# RS_Analog.net
KiCad netlist of a schematic drawn in Altium Designer
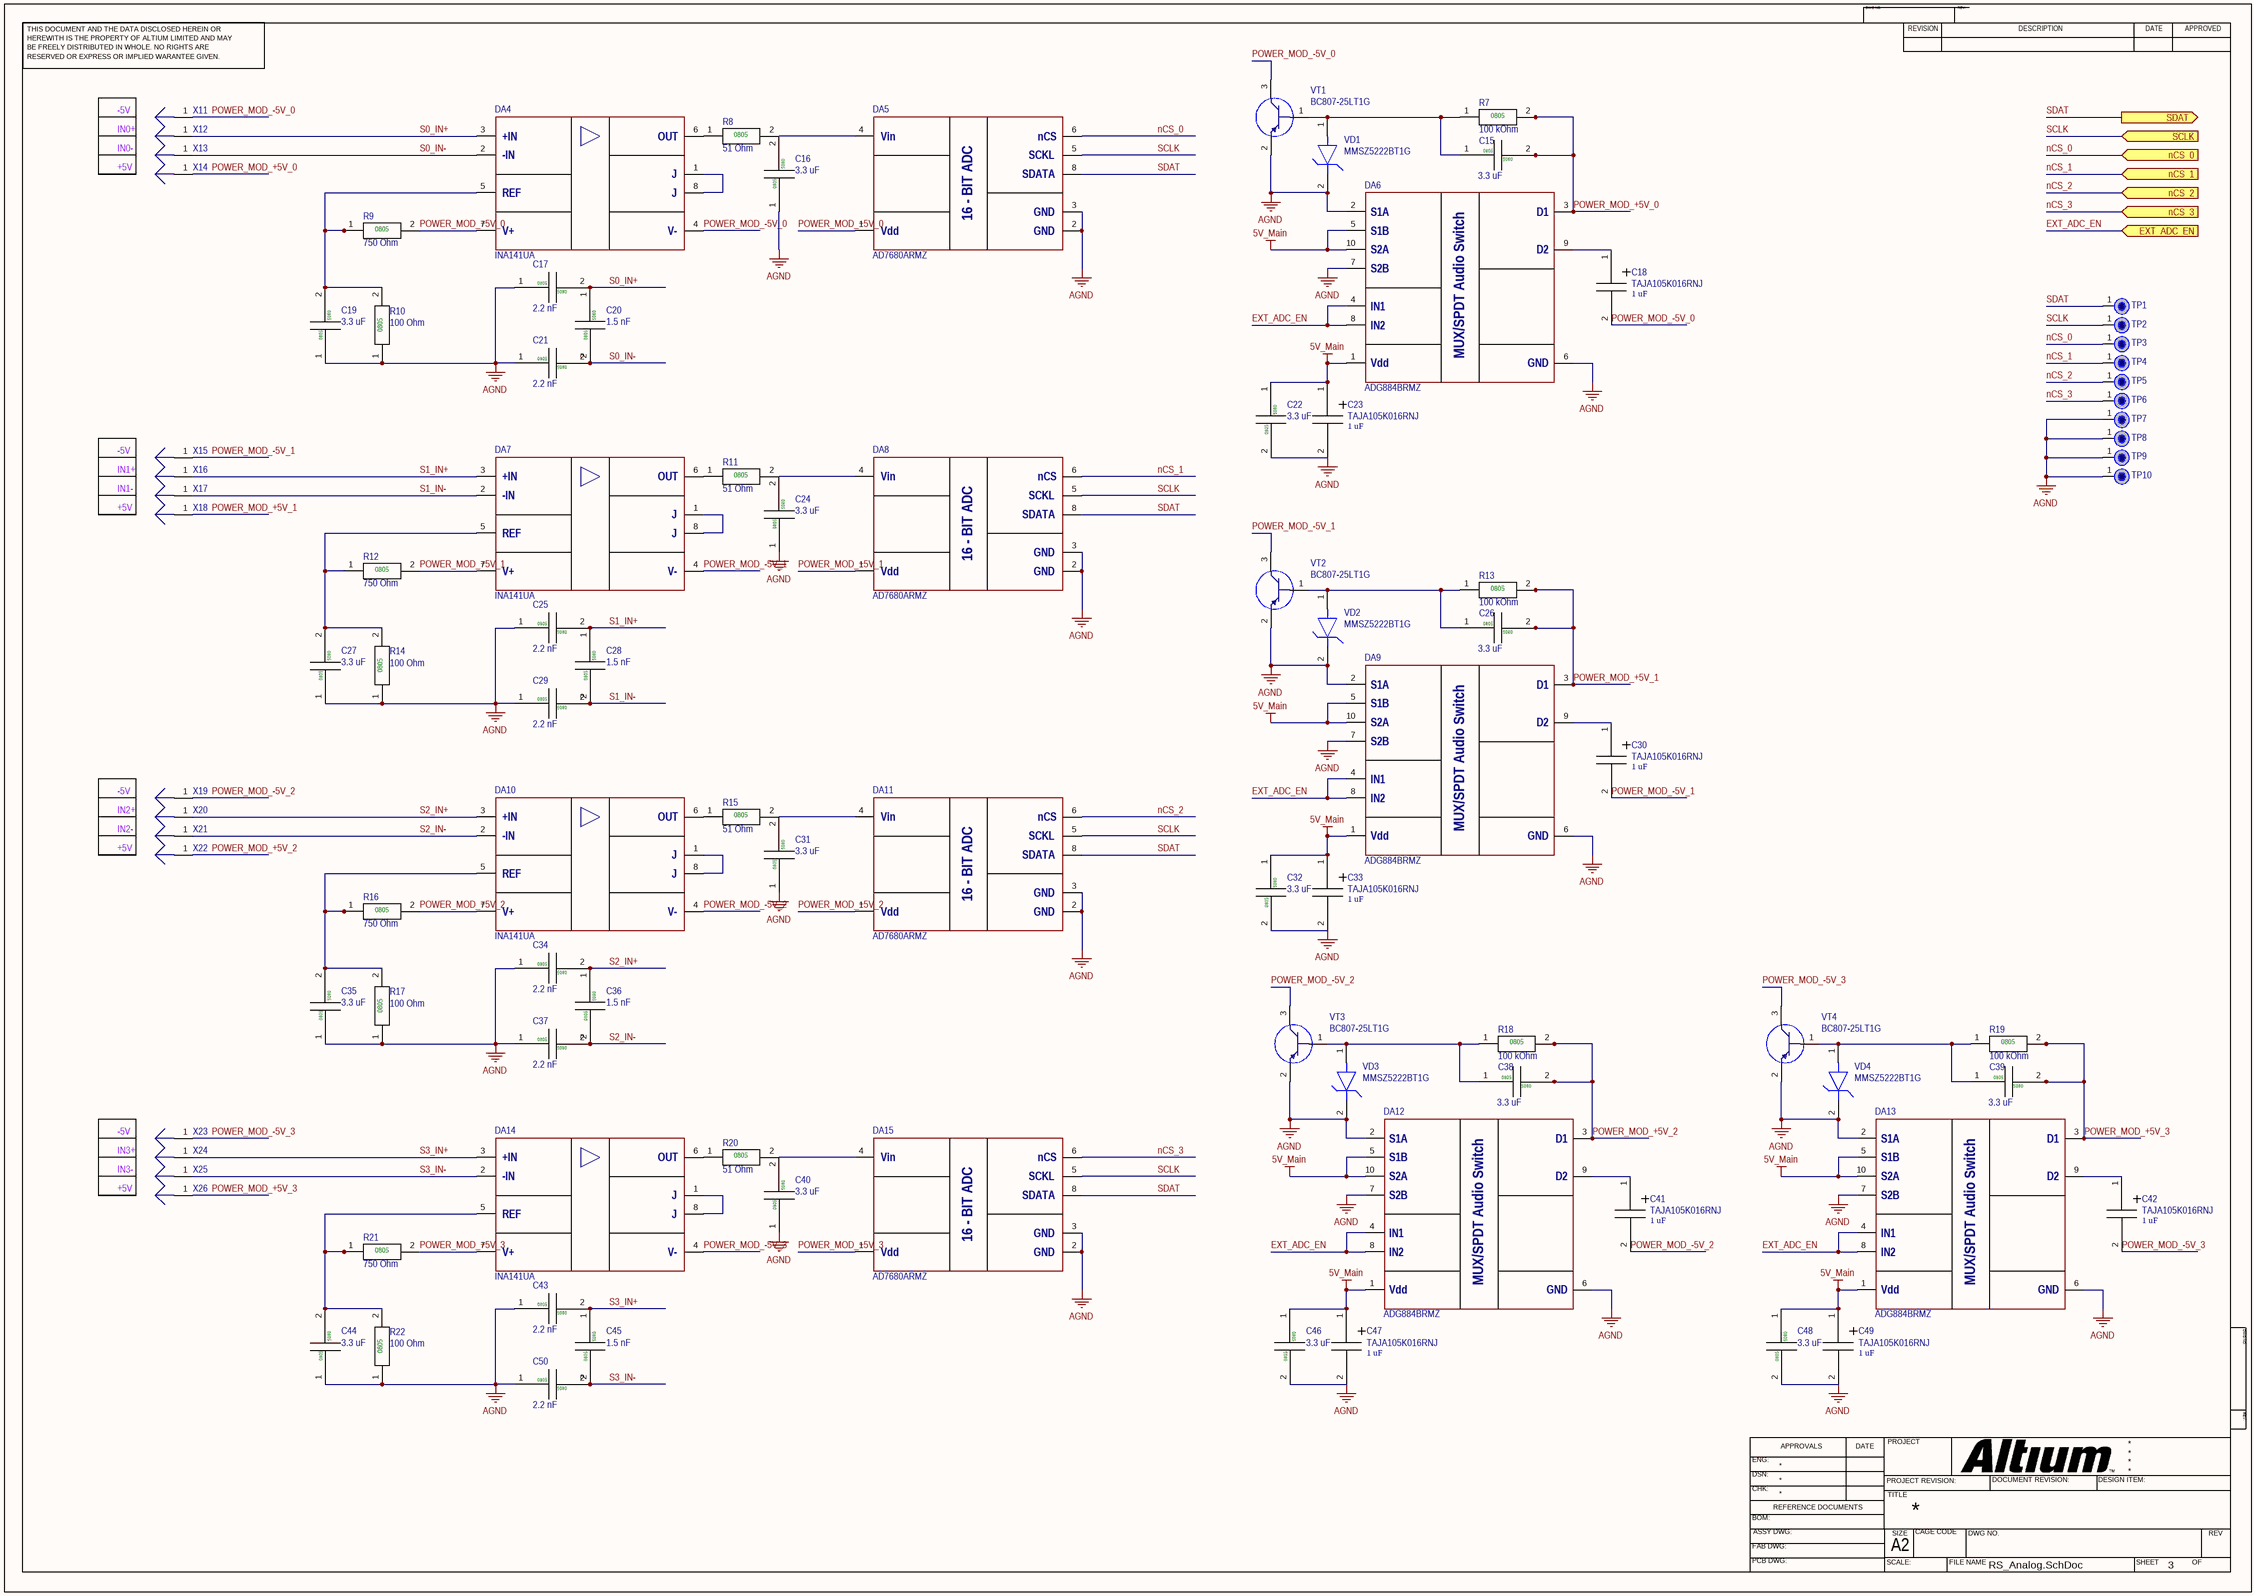
[diagram p0: RS_Analog.SchDoc]

(export (version "E")
  (design (tool "Eeschema 10.0.6"))
  (components
    (comp (ref "C15")
      (value "3.3 uF")
      (footprint "CAP: 0805")
      (description "16V 3.3uF X7R ±10% 0805 Multilayer Ceramic Capacitors MLCC - SMD/SMT ROHS")
      (fields
        (field (name "MANUFACTURER") "FH(Guangdong Fenghua Advanced Tech)")
        (field (name "VOLTAGE") "16 V")
      )
      (libsource (lib "CAP_Ceramic_0805(JLCPCB)") (part "3.3 uF 16V 10%"))
    )
    (comp (ref "C16")
      (value "3.3 uF")
      (footprint "CAP: 0805")
      (description "16V 3.3uF X7R ±10% 0805 Multilayer Ceramic Capacitors MLCC - SMD/SMT ROHS")
      (fields
        (field (name "MANUFACTURER") "FH(Guangdong Fenghua Advanced Tech)")
        (field (name "VOLTAGE") "16 V")
      )
      (libsource (lib "CAP_Ceramic_0805(JLCPCB)") (part "3.3 uF 16V 10%"))
    )
    (comp (ref "C17")
      (value "2.2 nF")
      (footprint "CAP: 0805")
      (description "50V 2.2nF X7R ±10% 0805 Multilayer Ceramic Capacitors MLCC - SMD/SMT ROHS")
      (fields (field (name "MANUFACTURER") "Samsung Electro-Mechanics") (field (name "VOLTAGE") "50 V"))
      (libsource (lib "CAP_Ceramic_0805(JLCPCB)") (part "2.2 nF 50V 10%"))
    )
    (comp (ref "C18")
      (value "TAJA105K016RNJ")
      (footprint "CAP: TANTAL-A")
      (description "1uF 16V -55℃~+125℃ ±10% CASE-A_3216 Tantalum Capacitors ROHS")
      (fields
        (field (name "MANUFACTURER") "AVX")
        (field (name "TOLERANCE") "10%")
        (field (name "CAPVALUE") "1 uF")
      )
      (libsource (lib "CAP_Tantalum") (part "1uF 16V 10%"))
    )
    (comp (ref "C19")
      (value "3.3 uF")
      (footprint "CAP: 0805")
      (description "16V 3.3uF X7R ±10% 0805 Multilayer Ceramic Capacitors MLCC - SMD/SMT ROHS")
      (fields
        (field (name "MANUFACTURER") "FH(Guangdong Fenghua Advanced Tech)")
        (field (name "VOLTAGE") "16 V")
      )
      (libsource (lib "CAP_Ceramic_0805(JLCPCB)") (part "3.3 uF 16V 10%"))
    )
    (comp (ref "C20")
      (value "1.5 nF")
      (footprint "CAP: 0805")
      (description "Ceramic capacitor 0805 surface mount")
      (fields (field (name "MANUFACTURER") "Samsung Electro-Mechanics") (field (name "VOLTAGE") "50 V"))
      (libsource (lib "CAP_Ceramic_0805(JLCPCB)") (part "1.5 nF 50V 20%(Ext)"))
    )
    (comp (ref "C21")
      (value "2.2 nF")
      (footprint "CAP: 0805")
      (description "50V 2.2nF X7R ±10% 0805 Multilayer Ceramic Capacitors MLCC - SMD/SMT ROHS")
      (fields (field (name "MANUFACTURER") "Samsung Electro-Mechanics") (field (name "VOLTAGE") "50 V"))
      (libsource (lib "CAP_Ceramic_0805(JLCPCB)") (part "2.2 nF 50V 10%"))
    )
    (comp (ref "C22")
      (value "3.3 uF")
      (footprint "CAP: 0805")
      (description "16V 3.3uF X7R ±10% 0805 Multilayer Ceramic Capacitors MLCC - SMD/SMT ROHS")
      (fields
        (field (name "MANUFACTURER") "FH(Guangdong Fenghua Advanced Tech)")
        (field (name "VOLTAGE") "16 V")
      )
      (libsource (lib "CAP_Ceramic_0805(JLCPCB)") (part "3.3 uF 16V 10%"))
    )
    (comp (ref "C23")
      (value "TAJA105K016RNJ")
      (footprint "CAP: TANTAL-A")
      (description "1uF 16V -55℃~+125℃ ±10% CASE-A_3216 Tantalum Capacitors ROHS")
      (fields
        (field (name "MANUFACTURER") "AVX")
        (field (name "TOLERANCE") "10%")
        (field (name "CAPVALUE") "1 uF")
      )
      (libsource (lib "CAP_Tantalum") (part "1uF 16V 10%"))
    )
    (comp (ref "C24")
      (value "3.3 uF")
      (footprint "CAP: 0805")
      (description "16V 3.3uF X7R ±10% 0805 Multilayer Ceramic Capacitors MLCC - SMD/SMT ROHS")
      (fields
        (field (name "MANUFACTURER") "FH(Guangdong Fenghua Advanced Tech)")
        (field (name "VOLTAGE") "16 V")
      )
      (libsource (lib "CAP_Ceramic_0805(JLCPCB)") (part "3.3 uF 16V 10%"))
    )
    (comp (ref "C25")
      (value "2.2 nF")
      (footprint "CAP: 0805")
      (description "50V 2.2nF X7R ±10% 0805 Multilayer Ceramic Capacitors MLCC - SMD/SMT ROHS")
      (fields (field (name "MANUFACTURER") "Samsung Electro-Mechanics") (field (name "VOLTAGE") "50 V"))
      (libsource (lib "CAP_Ceramic_0805(JLCPCB)") (part "2.2 nF 50V 10%"))
    )
    (comp (ref "C26")
      (value "3.3 uF")
      (footprint "CAP: 0805")
      (description "16V 3.3uF X7R ±10% 0805 Multilayer Ceramic Capacitors MLCC - SMD/SMT ROHS")
      (fields
        (field (name "MANUFACTURER") "FH(Guangdong Fenghua Advanced Tech)")
        (field (name "VOLTAGE") "16 V")
      )
      (libsource (lib "CAP_Ceramic_0805(JLCPCB)") (part "3.3 uF 16V 10%"))
    )
    (comp (ref "C27")
      (value "3.3 uF")
      (footprint "CAP: 0805")
      (description "16V 3.3uF X7R ±10% 0805 Multilayer Ceramic Capacitors MLCC - SMD/SMT ROHS")
      (fields
        (field (name "MANUFACTURER") "FH(Guangdong Fenghua Advanced Tech)")
        (field (name "VOLTAGE") "16 V")
      )
      (libsource (lib "CAP_Ceramic_0805(JLCPCB)") (part "3.3 uF 16V 10%"))
    )
    (comp (ref "C28")
      (value "1.5 nF")
      (footprint "CAP: 0805")
      (description "Ceramic capacitor 0805 surface mount")
      (fields (field (name "MANUFACTURER") "Samsung Electro-Mechanics") (field (name "VOLTAGE") "50 V"))
      (libsource (lib "CAP_Ceramic_0805(JLCPCB)") (part "1.5 nF 50V 20%(Ext)"))
    )
    (comp (ref "C29")
      (value "2.2 nF")
      (footprint "CAP: 0805")
      (description "50V 2.2nF X7R ±10% 0805 Multilayer Ceramic Capacitors MLCC - SMD/SMT ROHS")
      (fields (field (name "MANUFACTURER") "Samsung Electro-Mechanics") (field (name "VOLTAGE") "50 V"))
      (libsource (lib "CAP_Ceramic_0805(JLCPCB)") (part "2.2 nF 50V 10%"))
    )
    (comp (ref "C30")
      (value "TAJA105K016RNJ")
      (footprint "CAP: TANTAL-A")
      (description "1uF 16V -55℃~+125℃ ±10% CASE-A_3216 Tantalum Capacitors ROHS")
      (fields
        (field (name "MANUFACTURER") "AVX")
        (field (name "TOLERANCE") "10%")
        (field (name "CAPVALUE") "1 uF")
      )
      (libsource (lib "CAP_Tantalum") (part "1uF 16V 10%"))
    )
    (comp (ref "C31")
      (value "3.3 uF")
      (footprint "CAP: 0805")
      (description "16V 3.3uF X7R ±10% 0805 Multilayer Ceramic Capacitors MLCC - SMD/SMT ROHS")
      (fields
        (field (name "MANUFACTURER") "FH(Guangdong Fenghua Advanced Tech)")
        (field (name "VOLTAGE") "16 V")
      )
      (libsource (lib "CAP_Ceramic_0805(JLCPCB)") (part "3.3 uF 16V 10%"))
    )
    (comp (ref "C32")
      (value "3.3 uF")
      (footprint "CAP: 0805")
      (description "16V 3.3uF X7R ±10% 0805 Multilayer Ceramic Capacitors MLCC - SMD/SMT ROHS")
      (fields
        (field (name "MANUFACTURER") "FH(Guangdong Fenghua Advanced Tech)")
        (field (name "VOLTAGE") "16 V")
      )
      (libsource (lib "CAP_Ceramic_0805(JLCPCB)") (part "3.3 uF 16V 10%"))
    )
    (comp (ref "C33")
      (value "TAJA105K016RNJ")
      (footprint "CAP: TANTAL-A")
      (description "1uF 16V -55℃~+125℃ ±10% CASE-A_3216 Tantalum Capacitors ROHS")
      (fields
        (field (name "MANUFACTURER") "AVX")
        (field (name "TOLERANCE") "10%")
        (field (name "CAPVALUE") "1 uF")
      )
      (libsource (lib "CAP_Tantalum") (part "1uF 16V 10%"))
    )
    (comp (ref "C34")
      (value "2.2 nF")
      (footprint "CAP: 0805")
      (description "50V 2.2nF X7R ±10% 0805 Multilayer Ceramic Capacitors MLCC - SMD/SMT ROHS")
      (fields (field (name "MANUFACTURER") "Samsung Electro-Mechanics") (field (name "VOLTAGE") "50 V"))
      (libsource (lib "CAP_Ceramic_0805(JLCPCB)") (part "2.2 nF 50V 10%"))
    )
    (comp (ref "C35")
      (value "3.3 uF")
      (footprint "CAP: 0805")
      (description "16V 3.3uF X7R ±10% 0805 Multilayer Ceramic Capacitors MLCC - SMD/SMT ROHS")
      (fields
        (field (name "MANUFACTURER") "FH(Guangdong Fenghua Advanced Tech)")
        (field (name "VOLTAGE") "16 V")
      )
      (libsource (lib "CAP_Ceramic_0805(JLCPCB)") (part "3.3 uF 16V 10%"))
    )
    (comp (ref "C36")
      (value "1.5 nF")
      (footprint "CAP: 0805")
      (description "Ceramic capacitor 0805 surface mount")
      (fields (field (name "MANUFACTURER") "Samsung Electro-Mechanics") (field (name "VOLTAGE") "50 V"))
      (libsource (lib "CAP_Ceramic_0805(JLCPCB)") (part "1.5 nF 50V 20%(Ext)"))
    )
    (comp (ref "C37")
      (value "2.2 nF")
      (footprint "CAP: 0805")
      (description "50V 2.2nF X7R ±10% 0805 Multilayer Ceramic Capacitors MLCC - SMD/SMT ROHS")
      (fields (field (name "MANUFACTURER") "Samsung Electro-Mechanics") (field (name "VOLTAGE") "50 V"))
      (libsource (lib "CAP_Ceramic_0805(JLCPCB)") (part "2.2 nF 50V 10%"))
    )
    (comp (ref "C38")
      (value "3.3 uF")
      (footprint "CAP: 0805")
      (description "16V 3.3uF X7R ±10% 0805 Multilayer Ceramic Capacitors MLCC - SMD/SMT ROHS")
      (fields
        (field (name "MANUFACTURER") "FH(Guangdong Fenghua Advanced Tech)")
        (field (name "VOLTAGE") "16 V")
      )
      (libsource (lib "CAP_Ceramic_0805(JLCPCB)") (part "3.3 uF 16V 10%"))
    )
    (comp (ref "C39")
      (value "3.3 uF")
      (footprint "CAP: 0805")
      (description "16V 3.3uF X7R ±10% 0805 Multilayer Ceramic Capacitors MLCC - SMD/SMT ROHS")
      (fields
        (field (name "MANUFACTURER") "FH(Guangdong Fenghua Advanced Tech)")
        (field (name "VOLTAGE") "16 V")
      )
      (libsource (lib "CAP_Ceramic_0805(JLCPCB)") (part "3.3 uF 16V 10%"))
    )
    (comp (ref "C40")
      (value "3.3 uF")
      (footprint "CAP: 0805")
      (description "16V 3.3uF X7R ±10% 0805 Multilayer Ceramic Capacitors MLCC - SMD/SMT ROHS")
      (fields
        (field (name "MANUFACTURER") "FH(Guangdong Fenghua Advanced Tech)")
        (field (name "VOLTAGE") "16 V")
      )
      (libsource (lib "CAP_Ceramic_0805(JLCPCB)") (part "3.3 uF 16V 10%"))
    )
    (comp (ref "C41")
      (value "TAJA105K016RNJ")
      (footprint "CAP: TANTAL-A")
      (description "1uF 16V -55℃~+125℃ ±10% CASE-A_3216 Tantalum Capacitors ROHS")
      (fields
        (field (name "MANUFACTURER") "AVX")
        (field (name "TOLERANCE") "10%")
        (field (name "CAPVALUE") "1 uF")
      )
      (libsource (lib "CAP_Tantalum") (part "1uF 16V 10%"))
    )
    (comp (ref "C42")
      (value "TAJA105K016RNJ")
      (footprint "CAP: TANTAL-A")
      (description "1uF 16V -55℃~+125℃ ±10% CASE-A_3216 Tantalum Capacitors ROHS")
      (fields
        (field (name "MANUFACTURER") "AVX")
        (field (name "TOLERANCE") "10%")
        (field (name "CAPVALUE") "1 uF")
      )
      (libsource (lib "CAP_Tantalum") (part "1uF 16V 10%"))
    )
    (comp (ref "C43")
      (value "2.2 nF")
      (footprint "CAP: 0805")
      (description "50V 2.2nF X7R ±10% 0805 Multilayer Ceramic Capacitors MLCC - SMD/SMT ROHS")
      (fields (field (name "MANUFACTURER") "Samsung Electro-Mechanics") (field (name "VOLTAGE") "50 V"))
      (libsource (lib "CAP_Ceramic_0805(JLCPCB)") (part "2.2 nF 50V 10%"))
    )
    (comp (ref "C44")
      (value "3.3 uF")
      (footprint "CAP: 0805")
      (description "16V 3.3uF X7R ±10% 0805 Multilayer Ceramic Capacitors MLCC - SMD/SMT ROHS")
      (fields
        (field (name "MANUFACTURER") "FH(Guangdong Fenghua Advanced Tech)")
        (field (name "VOLTAGE") "16 V")
      )
      (libsource (lib "CAP_Ceramic_0805(JLCPCB)") (part "3.3 uF 16V 10%"))
    )
    (comp (ref "C45")
      (value "1.5 nF")
      (footprint "CAP: 0805")
      (description "Ceramic capacitor 0805 surface mount")
      (fields (field (name "MANUFACTURER") "Samsung Electro-Mechanics") (field (name "VOLTAGE") "50 V"))
      (libsource (lib "CAP_Ceramic_0805(JLCPCB)") (part "1.5 nF 50V 20%(Ext)"))
    )
    (comp (ref "C46")
      (value "3.3 uF")
      (footprint "CAP: 0805")
      (description "16V 3.3uF X7R ±10% 0805 Multilayer Ceramic Capacitors MLCC - SMD/SMT ROHS")
      (fields
        (field (name "MANUFACTURER") "FH(Guangdong Fenghua Advanced Tech)")
        (field (name "VOLTAGE") "16 V")
      )
      (libsource (lib "CAP_Ceramic_0805(JLCPCB)") (part "3.3 uF 16V 10%"))
    )
    (comp (ref "C47")
      (value "TAJA105K016RNJ")
      (footprint "CAP: TANTAL-A")
      (description "1uF 16V -55℃~+125℃ ±10% CASE-A_3216 Tantalum Capacitors ROHS")
      (fields
        (field (name "MANUFACTURER") "AVX")
        (field (name "TOLERANCE") "10%")
        (field (name "CAPVALUE") "1 uF")
      )
      (libsource (lib "CAP_Tantalum") (part "1uF 16V 10%"))
    )
    (comp (ref "C48")
      (value "3.3 uF")
      (footprint "CAP: 0805")
      (description "16V 3.3uF X7R ±10% 0805 Multilayer Ceramic Capacitors MLCC - SMD/SMT ROHS")
      (fields
        (field (name "MANUFACTURER") "FH(Guangdong Fenghua Advanced Tech)")
        (field (name "VOLTAGE") "16 V")
      )
      (libsource (lib "CAP_Ceramic_0805(JLCPCB)") (part "3.3 uF 16V 10%"))
    )
    (comp (ref "C49")
      (value "TAJA105K016RNJ")
      (footprint "CAP: TANTAL-A")
      (description "1uF 16V -55℃~+125℃ ±10% CASE-A_3216 Tantalum Capacitors ROHS")
      (fields
        (field (name "MANUFACTURER") "AVX")
        (field (name "TOLERANCE") "10%")
        (field (name "CAPVALUE") "1 uF")
      )
      (libsource (lib "CAP_Tantalum") (part "1uF 16V 10%"))
    )
    (comp (ref "C50")
      (value "2.2 nF")
      (footprint "CAP: 0805")
      (description "50V 2.2nF X7R ±10% 0805 Multilayer Ceramic Capacitors MLCC - SMD/SMT ROHS")
      (fields (field (name "MANUFACTURER") "Samsung Electro-Mechanics") (field (name "VOLTAGE") "50 V"))
      (libsource (lib "CAP_Ceramic_0805(JLCPCB)") (part "2.2 nF 50V 10%"))
    )
    (comp (ref "DA4")
      (value "INA141UA")
      (footprint "8-SOIC")
      (description "Precision, Low Power, G = 10, 100  INSTRUMENTATION AMPLIFIER")
      (fields (field (name "MANUFACTURER") "Texas Instruments") (field (name "LCS PART NUMBER") "C181633"))
      (libsource (lib "ICs_Analog") (part "INA141UA"))
    )
    (comp (ref "DA5")
      (value "AD7680ARMZ")
      (footprint "8-MSOP")
      (description "3 mW, 100 kSPS,  16-Bit ADC")
      (fields (field (name "MANUFACTURER") "Analog Devices") (field (name "LCS PART NUMBER") "C578464"))
      (libsource (lib "ICs_Analog") (part "AD7680ARMZ"))
    )
    (comp (ref "DA6")
      (value "ADG884BRMZ")
      (footprint "10-MSOP")
      (description "MSOP-10 Analog Switches / Multiplexers ROHS")
      (fields (field (name "MANUFACTURER") "Analog Devices") (field (name "LCS PART NUMBER") "C140435"))
      (libsource (lib "ICs_Analog") (part "ADG884BRMZ"))
    )
    (comp (ref "DA7")
      (value "INA141UA")
      (footprint "8-SOIC")
      (description "Precision, Low Power, G = 10, 100  INSTRUMENTATION AMPLIFIER")
      (fields (field (name "MANUFACTURER") "Texas Instruments") (field (name "LCS PART NUMBER") "C181633"))
      (libsource (lib "ICs_Analog") (part "INA141UA"))
    )
    (comp (ref "DA8")
      (value "AD7680ARMZ")
      (footprint "8-MSOP")
      (description "3 mW, 100 kSPS,  16-Bit ADC")
      (fields (field (name "MANUFACTURER") "Analog Devices") (field (name "LCS PART NUMBER") "C578464"))
      (libsource (lib "ICs_Analog") (part "AD7680ARMZ"))
    )
    (comp (ref "DA9")
      (value "ADG884BRMZ")
      (footprint "10-MSOP")
      (description "MSOP-10 Analog Switches / Multiplexers ROHS")
      (fields (field (name "MANUFACTURER") "Analog Devices") (field (name "LCS PART NUMBER") "C140435"))
      (libsource (lib "ICs_Analog") (part "ADG884BRMZ"))
    )
    (comp (ref "DA10")
      (value "INA141UA")
      (footprint "8-SOIC")
      (description "Precision, Low Power, G = 10, 100  INSTRUMENTATION AMPLIFIER")
      (fields (field (name "MANUFACTURER") "Texas Instruments") (field (name "LCS PART NUMBER") "C181633"))
      (libsource (lib "ICs_Analog") (part "INA141UA"))
    )
    (comp (ref "DA11")
      (value "AD7680ARMZ")
      (footprint "8-MSOP")
      (description "3 mW, 100 kSPS,  16-Bit ADC")
      (fields (field (name "MANUFACTURER") "Analog Devices") (field (name "LCS PART NUMBER") "C578464"))
      (libsource (lib "ICs_Analog") (part "AD7680ARMZ"))
    )
    (comp (ref "DA12")
      (value "ADG884BRMZ")
      (footprint "10-MSOP")
      (description "MSOP-10 Analog Switches / Multiplexers ROHS")
      (fields (field (name "MANUFACTURER") "Analog Devices") (field (name "LCS PART NUMBER") "C140435"))
      (libsource (lib "ICs_Analog") (part "ADG884BRMZ"))
    )
    (comp (ref "DA13")
      (value "ADG884BRMZ")
      (footprint "10-MSOP")
      (description "MSOP-10 Analog Switches / Multiplexers ROHS")
      (fields (field (name "MANUFACTURER") "Analog Devices") (field (name "LCS PART NUMBER") "C140435"))
      (libsource (lib "ICs_Analog") (part "ADG884BRMZ"))
    )
    (comp (ref "DA14")
      (value "INA141UA")
      (footprint "8-SOIC")
      (description "Precision, Low Power, G = 10, 100  INSTRUMENTATION AMPLIFIER")
      (fields (field (name "MANUFACTURER") "Texas Instruments") (field (name "LCS PART NUMBER") "C181633"))
      (libsource (lib "ICs_Analog") (part "INA141UA"))
    )
    (comp (ref "DA15")
      (value "AD7680ARMZ")
      (footprint "8-MSOP")
      (description "3 mW, 100 kSPS,  16-Bit ADC")
      (fields (field (name "MANUFACTURER") "Analog Devices") (field (name "LCS PART NUMBER") "C578464"))
      (libsource (lib "ICs_Analog") (part "AD7680ARMZ"))
    )
    (comp (ref "R7")
      (value "100 kOhm")
      (footprint "RES_0805")
      (description "LEAD-FREE THICK FILM CHIP RESISTORS")
      (fields (field (name "MANUFACTURER") "Uniroyal Elec") (field (name "TOLERANCE") "1%"))
      (libsource (lib "RES_SMD_0805(JLCPCB)") (part "100k 1% 1/8W"))
    )
    (comp (ref "R8")
      (value "51 Ohm")
      (footprint "RES: 0805")
      (fields
        (field (name "MANUFACTURER") "Uniroyal Elec")
        (field (name "TOLERANCE") "1%")
        (field (name "POWER") "1/8 W")
      )
      (libsource (lib "RES_SMD_0805(JLCPCB)") (part "51R 1% 1/8W"))
    )
    (comp (ref "R9")
      (value "750 Ohm")
      (footprint "RES: 0805")
      (fields
        (field (name "MANUFACTURER") "Uniroyal Elec")
        (field (name "TOLERANCE") "1%")
        (field (name "POWER") "1/8 W")
      )
      (libsource (lib "RES_SMD_0805(JLCPCB)") (part "750R 1% 1/8W"))
    )
    (comp (ref "R10")
      (value "100 Ohm")
      (footprint "RES: 0805")
      (description "LEAD-FREE THICK FILM CHIP RESISTORS")
      (fields (field (name "MANUFACTURER") "Uniroyal Elec") (field (name "TOLERANCE") "1%"))
      (libsource (lib "RES_SMD_0805(JLCPCB)") (part "100R 1% 1/8W"))
    )
    (comp (ref "R11")
      (value "51 Ohm")
      (footprint "RES: 0805")
      (fields
        (field (name "MANUFACTURER") "Uniroyal Elec")
        (field (name "TOLERANCE") "1%")
        (field (name "POWER") "1/8 W")
      )
      (libsource (lib "RES_SMD_0805(JLCPCB)") (part "51R 1% 1/8W"))
    )
    (comp (ref "R12")
      (value "750 Ohm")
      (footprint "RES: 0805")
      (fields
        (field (name "MANUFACTURER") "Uniroyal Elec")
        (field (name "TOLERANCE") "1%")
        (field (name "POWER") "1/8 W")
      )
      (libsource (lib "RES_SMD_0805(JLCPCB)") (part "750R 1% 1/8W"))
    )
    (comp (ref "R13")
      (value "100 kOhm")
      (footprint "RES_0805")
      (description "LEAD-FREE THICK FILM CHIP RESISTORS")
      (fields (field (name "MANUFACTURER") "Uniroyal Elec") (field (name "TOLERANCE") "1%"))
      (libsource (lib "RES_SMD_0805(JLCPCB)") (part "100k 1% 1/8W"))
    )
    (comp (ref "R14")
      (value "100 Ohm")
      (footprint "RES: 0805")
      (description "LEAD-FREE THICK FILM CHIP RESISTORS")
      (fields (field (name "MANUFACTURER") "Uniroyal Elec") (field (name "TOLERANCE") "1%"))
      (libsource (lib "RES_SMD_0805(JLCPCB)") (part "100R 1% 1/8W"))
    )
    (comp (ref "R15")
      (value "51 Ohm")
      (footprint "RES: 0805")
      (fields
        (field (name "MANUFACTURER") "Uniroyal Elec")
        (field (name "TOLERANCE") "1%")
        (field (name "POWER") "1/8 W")
      )
      (libsource (lib "RES_SMD_0805(JLCPCB)") (part "51R 1% 1/8W"))
    )
    (comp (ref "R16")
      (value "750 Ohm")
      (footprint "RES: 0805")
      (fields
        (field (name "MANUFACTURER") "Uniroyal Elec")
        (field (name "TOLERANCE") "1%")
        (field (name "POWER") "1/8 W")
      )
      (libsource (lib "RES_SMD_0805(JLCPCB)") (part "750R 1% 1/8W"))
    )
    (comp (ref "R17")
      (value "100 Ohm")
      (footprint "RES: 0805")
      (description "LEAD-FREE THICK FILM CHIP RESISTORS")
      (fields (field (name "MANUFACTURER") "Uniroyal Elec") (field (name "TOLERANCE") "1%"))
      (libsource (lib "RES_SMD_0805(JLCPCB)") (part "100R 1% 1/8W"))
    )
    (comp (ref "R18")
      (value "100 kOhm")
      (footprint "RES_0805")
      (description "LEAD-FREE THICK FILM CHIP RESISTORS")
      (fields (field (name "MANUFACTURER") "Uniroyal Elec") (field (name "TOLERANCE") "1%"))
      (libsource (lib "RES_SMD_0805(JLCPCB)") (part "100k 1% 1/8W"))
    )
    (comp (ref "R19")
      (value "100 kOhm")
      (footprint "RES_0805")
      (description "LEAD-FREE THICK FILM CHIP RESISTORS")
      (fields (field (name "MANUFACTURER") "Uniroyal Elec") (field (name "TOLERANCE") "1%"))
      (libsource (lib "RES_SMD_0805(JLCPCB)") (part "100k 1% 1/8W"))
    )
    (comp (ref "R20")
      (value "51 Ohm")
      (footprint "RES: 0805")
      (fields
        (field (name "MANUFACTURER") "Uniroyal Elec")
        (field (name "TOLERANCE") "1%")
        (field (name "POWER") "1/8 W")
      )
      (libsource (lib "RES_SMD_0805(JLCPCB)") (part "51R 1% 1/8W"))
    )
    (comp (ref "R21")
      (value "750 Ohm")
      (footprint "RES: 0805")
      (fields
        (field (name "MANUFACTURER") "Uniroyal Elec")
        (field (name "TOLERANCE") "1%")
        (field (name "POWER") "1/8 W")
      )
      (libsource (lib "RES_SMD_0805(JLCPCB)") (part "750R 1% 1/8W"))
    )
    (comp (ref "R22")
      (value "100 Ohm")
      (footprint "RES: 0805")
      (description "LEAD-FREE THICK FILM CHIP RESISTORS")
      (fields (field (name "MANUFACTURER") "Uniroyal Elec") (field (name "TOLERANCE") "1%"))
      (libsource (lib "RES_SMD_0805(JLCPCB)") (part "100R 1% 1/8W"))
    )
    (comp (ref "TP1")
      (value "TestPoint")
      (footprint "TestPoint")
      (libsource (lib "Connectors&PinHeaders") (part "TestPoint"))
    )
    (comp (ref "TP2")
      (value "TestPoint")
      (footprint "TestPoint")
      (libsource (lib "Connectors&PinHeaders") (part "TestPoint"))
    )
    (comp (ref "TP3")
      (value "TestPoint")
      (footprint "TestPoint")
      (libsource (lib "Connectors&PinHeaders") (part "TestPoint"))
    )
    (comp (ref "TP4")
      (value "TestPoint")
      (footprint "TestPoint")
      (libsource (lib "Connectors&PinHeaders") (part "TestPoint"))
    )
    (comp (ref "TP5")
      (value "TestPoint")
      (footprint "TestPoint")
      (libsource (lib "Connectors&PinHeaders") (part "TestPoint"))
    )
    (comp (ref "TP6")
      (value "TestPoint")
      (footprint "TestPoint")
      (libsource (lib "Connectors&PinHeaders") (part "TestPoint"))
    )
    (comp (ref "TP7")
      (value "TestPoint")
      (footprint "TestPoint")
      (libsource (lib "Connectors&PinHeaders") (part "TestPoint"))
    )
    (comp (ref "TP8")
      (value "TestPoint")
      (footprint "TestPoint")
      (libsource (lib "Connectors&PinHeaders") (part "TestPoint"))
    )
    (comp (ref "TP9")
      (value "TestPoint")
      (footprint "TestPoint")
      (libsource (lib "Connectors&PinHeaders") (part "TestPoint"))
    )
    (comp (ref "TP10")
      (value "TestPoint")
      (footprint "TestPoint")
      (libsource (lib "Connectors&PinHeaders") (part "TestPoint"))
    )
    (comp (ref "VD1")
      (value "MMSZ5222BT1G")
      (footprint "DIODE: SOD123")
      (description "100μA@1V ±5% 30Ω Single 2.38V~2.63V 500mW 2.5V SOD-123 Zener Diodes ROHS")
      (fields (field (name "LCSC PART NUMBER") "C150078") (field (name "MANUFACTURER") "onsemi"))
      (libsource (lib "Diodes") (part "MMSZ5222BT1G"))
    )
    (comp (ref "VD2")
      (value "MMSZ5222BT1G")
      (footprint "DIODE: SOD123")
      (description "100μA@1V ±5% 30Ω Single 2.38V~2.63V 500mW 2.5V SOD-123 Zener Diodes ROHS")
      (fields (field (name "LCSC PART NUMBER") "C150078") (field (name "MANUFACTURER") "onsemi"))
      (libsource (lib "Diodes") (part "MMSZ5222BT1G"))
    )
    (comp (ref "VD3")
      (value "MMSZ5222BT1G")
      (footprint "DIODE: SOD123")
      (description "100μA@1V ±5% 30Ω Single 2.38V~2.63V 500mW 2.5V SOD-123 Zener Diodes ROHS")
      (fields (field (name "LCSC PART NUMBER") "C150078") (field (name "MANUFACTURER") "onsemi"))
      (libsource (lib "Diodes") (part "MMSZ5222BT1G"))
    )
    (comp (ref "VD4")
      (value "MMSZ5222BT1G")
      (footprint "DIODE: SOD123")
      (description "100μA@1V ±5% 30Ω Single 2.38V~2.63V 500mW 2.5V SOD-123 Zener Diodes ROHS")
      (fields (field (name "LCSC PART NUMBER") "C150078") (field (name "MANUFACTURER") "onsemi"))
      (libsource (lib "Diodes") (part "MMSZ5222BT1G"))
    )
    (comp (ref "VT1")
      (value "BC807-25LT1G")
      (footprint "SOT23")
      (fields (field (name "MANUFACTURER") "ON Semiconductor") (field (name "LCSC PART NUMBER") "C152312"))
      (libsource (lib "Transistors(Bipolar)") (part "BC807-25LT1G"))
    )
    (comp (ref "VT2")
      (value "BC807-25LT1G")
      (footprint "SOT23")
      (fields (field (name "MANUFACTURER") "ON Semiconductor") (field (name "LCSC PART NUMBER") "C152312"))
      (libsource (lib "Transistors(Bipolar)") (part "BC807-25LT1G"))
    )
    (comp (ref "VT3")
      (value "BC807-25LT1G")
      (footprint "SOT23")
      (fields (field (name "MANUFACTURER") "ON Semiconductor") (field (name "LCSC PART NUMBER") "C152312"))
      (libsource (lib "Transistors(Bipolar)") (part "BC807-25LT1G"))
    )
    (comp (ref "VT4")
      (value "BC807-25LT1G")
      (footprint "SOT23")
      (fields (field (name "MANUFACTURER") "ON Semiconductor") (field (name "LCSC PART NUMBER") "C152312"))
      (libsource (lib "Transistors(Bipolar)") (part "BC807-25LT1G"))
    )
    (comp (ref "X11")
      (value "*")
      (footprint "PowerSingle")
      (libsource (lib "Connectors&PinHeaders") (part "PowerSingleHole"))
    )
    (comp (ref "X12")
      (value "*")
      (footprint "PowerSingle")
      (libsource (lib "Connectors&PinHeaders") (part "PowerSingleHole"))
    )
    (comp (ref "X13")
      (value "*")
      (footprint "PowerSingle")
      (libsource (lib "Connectors&PinHeaders") (part "PowerSingleHole"))
    )
    (comp (ref "X14")
      (value "*")
      (footprint "PowerSingle")
      (libsource (lib "Connectors&PinHeaders") (part "PowerSingleHole"))
    )
    (comp (ref "X15")
      (value "*")
      (footprint "PowerSingle")
      (libsource (lib "Connectors&PinHeaders") (part "PowerSingleHole"))
    )
    (comp (ref "X16")
      (value "*")
      (footprint "PowerSingle")
      (libsource (lib "Connectors&PinHeaders") (part "PowerSingleHole"))
    )
    (comp (ref "X17")
      (value "*")
      (footprint "PowerSingle")
      (libsource (lib "Connectors&PinHeaders") (part "PowerSingleHole"))
    )
    (comp (ref "X18")
      (value "*")
      (footprint "PowerSingle")
      (libsource (lib "Connectors&PinHeaders") (part "PowerSingleHole"))
    )
    (comp (ref "X19")
      (value "*")
      (footprint "PowerSingle")
      (libsource (lib "Connectors&PinHeaders") (part "PowerSingleHole"))
    )
    (comp (ref "X20")
      (value "*")
      (footprint "PowerSingle")
      (libsource (lib "Connectors&PinHeaders") (part "PowerSingleHole"))
    )
    (comp (ref "X21")
      (value "*")
      (footprint "PowerSingle")
      (libsource (lib "Connectors&PinHeaders") (part "PowerSingleHole"))
    )
    (comp (ref "X22")
      (value "*")
      (footprint "PowerSingle")
      (libsource (lib "Connectors&PinHeaders") (part "PowerSingleHole"))
    )
    (comp (ref "X23")
      (value "*")
      (footprint "PowerSingle")
      (libsource (lib "Connectors&PinHeaders") (part "PowerSingleHole"))
    )
    (comp (ref "X24")
      (value "*")
      (footprint "PowerSingle")
      (libsource (lib "Connectors&PinHeaders") (part "PowerSingleHole"))
    )
    (comp (ref "X25")
      (value "*")
      (footprint "PowerSingle")
      (libsource (lib "Connectors&PinHeaders") (part "PowerSingleHole"))
    )
    (comp (ref "X26")
      (value "*")
      (footprint "PowerSingle")
      (libsource (lib "Connectors&PinHeaders") (part "PowerSingleHole"))
    )
  )
  (nets
    (net (code "1") (name "/EXT_ADC_EN") (class "Default")
      (node (ref "DA12") (pin "4") (pinfunction "IN1_4") (pintype "passive"))
      (node (ref "DA12") (pin "8") (pinfunction "IN2_8") (pintype "passive"))
      (node (ref "DA13") (pin "4") (pinfunction "IN1_4") (pintype "passive"))
      (node (ref "DA13") (pin "8") (pinfunction "IN2_8") (pintype "passive"))
      (node (ref "DA6") (pin "4") (pinfunction "IN1_4") (pintype "passive"))
      (node (ref "DA6") (pin "8") (pinfunction "IN2_8") (pintype "passive"))
      (node (ref "DA9") (pin "4") (pinfunction "IN1_4") (pintype "passive"))
      (node (ref "DA9") (pin "8") (pinfunction "IN2_8") (pintype "passive"))
    )
    (net (code "2") (name "/POWER_MOD_+5V_0") (class "Default")
      (node (ref "C15") (pin "2") (pintype "passive"))
      (node (ref "DA4") (pin "7") (pinfunction "V+_7") (pintype "passive"))
      (node (ref "DA5") (pin "1") (pinfunction "Vdd_1") (pintype "passive"))
      (node (ref "DA6") (pin "3") (pinfunction "D1_3") (pintype "passive"))
      (node (ref "R7") (pin "2") (pintype "passive"))
      (node (ref "R9") (pin "2") (pintype "passive"))
      (node (ref "X14") (pin "1") (pinfunction "1_1") (pintype "passive"))
    )
    (net (code "3") (name "/POWER_MOD_+5V_1") (class "Default")
      (node (ref "C26") (pin "2") (pintype "passive"))
      (node (ref "DA7") (pin "7") (pinfunction "V+_7") (pintype "passive"))
      (node (ref "DA8") (pin "1") (pinfunction "Vdd_1") (pintype "passive"))
      (node (ref "DA9") (pin "3") (pinfunction "D1_3") (pintype "passive"))
      (node (ref "R12") (pin "2") (pintype "passive"))
      (node (ref "R13") (pin "2") (pintype "passive"))
      (node (ref "X18") (pin "1") (pinfunction "1_1") (pintype "passive"))
    )
    (net (code "4") (name "/POWER_MOD_+5V_2") (class "Default")
      (node (ref "C38") (pin "2") (pintype "passive"))
      (node (ref "DA10") (pin "7") (pinfunction "V+_7") (pintype "passive"))
      (node (ref "DA11") (pin "1") (pinfunction "Vdd_1") (pintype "passive"))
      (node (ref "DA12") (pin "3") (pinfunction "D1_3") (pintype "passive"))
      (node (ref "R16") (pin "2") (pintype "passive"))
      (node (ref "R18") (pin "2") (pintype "passive"))
      (node (ref "X22") (pin "1") (pinfunction "1_1") (pintype "passive"))
    )
    (net (code "5") (name "/POWER_MOD_+5V_3") (class "Default")
      (node (ref "C39") (pin "2") (pintype "passive"))
      (node (ref "DA13") (pin "3") (pinfunction "D1_3") (pintype "passive"))
      (node (ref "DA14") (pin "7") (pinfunction "V+_7") (pintype "passive"))
      (node (ref "DA15") (pin "1") (pinfunction "Vdd_1") (pintype "passive"))
      (node (ref "R19") (pin "2") (pintype "passive"))
      (node (ref "R21") (pin "2") (pintype "passive"))
      (node (ref "X26") (pin "1") (pinfunction "1_1") (pintype "passive"))
    )
    (net (code "6") (name "/POWER_MOD_-5V_0") (class "Default")
      (node (ref "C18") (pin "2") (pintype "passive"))
      (node (ref "DA4") (pin "4") (pinfunction "V-_4") (pintype "passive"))
      (node (ref "VT1") (pin "3") (pinfunction "Drain_3") (pintype "passive"))
      (node (ref "X11") (pin "1") (pinfunction "1_1") (pintype "passive"))
    )
    (net (code "7") (name "/POWER_MOD_-5V_1") (class "Default")
      (node (ref "C30") (pin "2") (pintype "passive"))
      (node (ref "DA7") (pin "4") (pinfunction "V-_4") (pintype "passive"))
      (node (ref "VT2") (pin "3") (pinfunction "Drain_3") (pintype "passive"))
      (node (ref "X15") (pin "1") (pinfunction "1_1") (pintype "passive"))
    )
    (net (code "8") (name "/POWER_MOD_-5V_2") (class "Default")
      (node (ref "C41") (pin "2") (pintype "passive"))
      (node (ref "DA10") (pin "4") (pinfunction "V-_4") (pintype "passive"))
      (node (ref "VT3") (pin "3") (pinfunction "Drain_3") (pintype "passive"))
      (node (ref "X19") (pin "1") (pinfunction "1_1") (pintype "passive"))
    )
    (net (code "9") (name "/POWER_MOD_-5V_3") (class "Default")
      (node (ref "C42") (pin "2") (pintype "passive"))
      (node (ref "DA14") (pin "4") (pinfunction "V-_4") (pintype "passive"))
      (node (ref "VT4") (pin "3") (pinfunction "Drain_3") (pintype "passive"))
      (node (ref "X23") (pin "1") (pinfunction "1_1") (pintype "passive"))
    )
    (net (code "10") (name "/S0_IN+") (class "Default")
      (node (ref "C17") (pin "2") (pintype "passive"))
      (node (ref "C20") (pin "1") (pintype "passive"))
      (node (ref "DA4") (pin "3") (pinfunction "+IN_3") (pintype "passive"))
      (node (ref "X12") (pin "1") (pinfunction "1_1") (pintype "passive"))
    )
    (net (code "11") (name "/S0_IN-") (class "Default")
      (node (ref "C20") (pin "2") (pintype "passive"))
      (node (ref "C21") (pin "2") (pintype "passive"))
      (node (ref "DA4") (pin "2") (pinfunction "-IN_2") (pintype "passive"))
      (node (ref "X13") (pin "1") (pinfunction "1_1") (pintype "passive"))
    )
    (net (code "12") (name "/S1_IN+") (class "Default")
      (node (ref "C25") (pin "2") (pintype "passive"))
      (node (ref "C28") (pin "1") (pintype "passive"))
      (node (ref "DA7") (pin "3") (pinfunction "+IN_3") (pintype "passive"))
      (node (ref "X16") (pin "1") (pinfunction "1_1") (pintype "passive"))
    )
    (net (code "13") (name "/S1_IN-") (class "Default")
      (node (ref "C28") (pin "2") (pintype "passive"))
      (node (ref "C29") (pin "2") (pintype "passive"))
      (node (ref "DA7") (pin "2") (pinfunction "-IN_2") (pintype "passive"))
      (node (ref "X17") (pin "1") (pinfunction "1_1") (pintype "passive"))
    )
    (net (code "14") (name "/S2_IN+") (class "Default")
      (node (ref "C34") (pin "2") (pintype "passive"))
      (node (ref "C36") (pin "1") (pintype "passive"))
      (node (ref "DA10") (pin "3") (pinfunction "+IN_3") (pintype "passive"))
      (node (ref "X20") (pin "1") (pinfunction "1_1") (pintype "passive"))
    )
    (net (code "15") (name "/S2_IN-") (class "Default")
      (node (ref "C36") (pin "2") (pintype "passive"))
      (node (ref "C37") (pin "2") (pintype "passive"))
      (node (ref "DA10") (pin "2") (pinfunction "-IN_2") (pintype "passive"))
      (node (ref "X21") (pin "1") (pinfunction "1_1") (pintype "passive"))
    )
    (net (code "16") (name "/S3_IN+") (class "Default")
      (node (ref "C43") (pin "2") (pintype "passive"))
      (node (ref "C45") (pin "1") (pintype "passive"))
      (node (ref "DA14") (pin "3") (pinfunction "+IN_3") (pintype "passive"))
      (node (ref "X24") (pin "1") (pinfunction "1_1") (pintype "passive"))
    )
    (net (code "17") (name "/S3_IN-") (class "Default")
      (node (ref "C45") (pin "2") (pintype "passive"))
      (node (ref "C50") (pin "2") (pintype "passive"))
      (node (ref "DA14") (pin "2") (pinfunction "-IN_2") (pintype "passive"))
      (node (ref "X25") (pin "1") (pinfunction "1_1") (pintype "passive"))
    )
    (net (code "18") (name "/SCLK") (class "Default")
      (node (ref "DA11") (pin "5") (pinfunction "SCKL_5") (pintype "passive"))
      (node (ref "DA15") (pin "5") (pinfunction "SCKL_5") (pintype "passive"))
      (node (ref "DA5") (pin "5") (pinfunction "SCKL_5") (pintype "passive"))
      (node (ref "DA8") (pin "5") (pinfunction "SCKL_5") (pintype "passive"))
      (node (ref "TP2") (pin "1") (pinfunction "1_1") (pintype "passive"))
    )
    (net (code "19") (name "/SDAT") (class "Default")
      (node (ref "DA11") (pin "8") (pinfunction "SDATA_8") (pintype "passive"))
      (node (ref "DA15") (pin "8") (pinfunction "SDATA_8") (pintype "passive"))
      (node (ref "DA5") (pin "8") (pinfunction "SDATA_8") (pintype "passive"))
      (node (ref "DA8") (pin "8") (pinfunction "SDATA_8") (pintype "passive"))
      (node (ref "TP1") (pin "1") (pinfunction "1_1") (pintype "passive"))
    )
    (net (code "20") (name "/nCS_0") (class "Default")
      (node (ref "DA5") (pin "6") (pinfunction "nCS_6") (pintype "passive"))
      (node (ref "TP3") (pin "1") (pinfunction "1_1") (pintype "passive"))
    )
    (net (code "21") (name "/nCS_1") (class "Default")
      (node (ref "DA8") (pin "6") (pinfunction "nCS_6") (pintype "passive"))
      (node (ref "TP4") (pin "1") (pinfunction "1_1") (pintype "passive"))
    )
    (net (code "22") (name "/nCS_2") (class "Default")
      (node (ref "DA11") (pin "6") (pinfunction "nCS_6") (pintype "passive"))
      (node (ref "TP5") (pin "1") (pinfunction "1_1") (pintype "passive"))
    )
    (net (code "23") (name "/nCS_3") (class "Default")
      (node (ref "DA15") (pin "6") (pinfunction "nCS_6") (pintype "passive"))
      (node (ref "TP6") (pin "1") (pinfunction "1_1") (pintype "passive"))
    )
    (net (code "24") (name "5V_Main") (class "Default")
      (node (ref "C22") (pin "1") (pintype "passive"))
      (node (ref "C23") (pin "1") (pintype "passive"))
      (node (ref "C32") (pin "1") (pintype "passive"))
      (node (ref "C33") (pin "1") (pintype "passive"))
      (node (ref "C46") (pin "1") (pintype "passive"))
      (node (ref "C47") (pin "1") (pintype "passive"))
      (node (ref "C48") (pin "1") (pintype "passive"))
      (node (ref "C49") (pin "1") (pintype "passive"))
      (node (ref "DA12") (pin "1") (pinfunction "Vdd_1") (pintype "passive"))
      (node (ref "DA12") (pin "10") (pinfunction "S2A_10") (pintype "passive"))
      (node (ref "DA12") (pin "5") (pinfunction "S1B_5") (pintype "passive"))
      (node (ref "DA13") (pin "1") (pinfunction "Vdd_1") (pintype "passive"))
      (node (ref "DA13") (pin "10") (pinfunction "S2A_10") (pintype "passive"))
      (node (ref "DA13") (pin "5") (pinfunction "S1B_5") (pintype "passive"))
      (node (ref "DA6") (pin "1") (pinfunction "Vdd_1") (pintype "passive"))
      (node (ref "DA6") (pin "10") (pinfunction "S2A_10") (pintype "passive"))
      (node (ref "DA6") (pin "5") (pinfunction "S1B_5") (pintype "passive"))
      (node (ref "DA9") (pin "1") (pinfunction "Vdd_1") (pintype "passive"))
      (node (ref "DA9") (pin "10") (pinfunction "S2A_10") (pintype "passive"))
      (node (ref "DA9") (pin "5") (pinfunction "S1B_5") (pintype "passive"))
    )
    (net (code "25") (name "AGND") (class "Default")
      (node (ref "C16") (pin "1") (pintype "passive"))
      (node (ref "C17") (pin "1") (pintype "passive"))
      (node (ref "C19") (pin "1") (pintype "passive"))
      (node (ref "C21") (pin "1") (pintype "passive"))
      (node (ref "C22") (pin "2") (pintype "passive"))
      (node (ref "C23") (pin "2") (pintype "passive"))
      (node (ref "C24") (pin "1") (pintype "passive"))
      (node (ref "C25") (pin "1") (pintype "passive"))
      (node (ref "C27") (pin "1") (pintype "passive"))
      (node (ref "C29") (pin "1") (pintype "passive"))
      (node (ref "C31") (pin "1") (pintype "passive"))
      (node (ref "C32") (pin "2") (pintype "passive"))
      (node (ref "C33") (pin "2") (pintype "passive"))
      (node (ref "C34") (pin "1") (pintype "passive"))
      (node (ref "C35") (pin "1") (pintype "passive"))
      (node (ref "C37") (pin "1") (pintype "passive"))
      (node (ref "C40") (pin "1") (pintype "passive"))
      (node (ref "C43") (pin "1") (pintype "passive"))
      (node (ref "C44") (pin "1") (pintype "passive"))
      (node (ref "C46") (pin "2") (pintype "passive"))
      (node (ref "C47") (pin "2") (pintype "passive"))
      (node (ref "C48") (pin "2") (pintype "passive"))
      (node (ref "C49") (pin "2") (pintype "passive"))
      (node (ref "C50") (pin "1") (pintype "passive"))
      (node (ref "DA11") (pin "2") (pinfunction "GND_2") (pintype "passive"))
      (node (ref "DA11") (pin "3") (pinfunction "GND_3") (pintype "passive"))
      (node (ref "DA12") (pin "2") (pinfunction "S1A_2") (pintype "passive"))
      (node (ref "DA12") (pin "6") (pinfunction "GND_6") (pintype "passive"))
      (node (ref "DA12") (pin "7") (pinfunction "S2B_7") (pintype "passive"))
      (node (ref "DA13") (pin "2") (pinfunction "S1A_2") (pintype "passive"))
      (node (ref "DA13") (pin "6") (pinfunction "GND_6") (pintype "passive"))
      (node (ref "DA13") (pin "7") (pinfunction "S2B_7") (pintype "passive"))
      (node (ref "DA15") (pin "2") (pinfunction "GND_2") (pintype "passive"))
      (node (ref "DA15") (pin "3") (pinfunction "GND_3") (pintype "passive"))
      (node (ref "DA5") (pin "2") (pinfunction "GND_2") (pintype "passive"))
      (node (ref "DA5") (pin "3") (pinfunction "GND_3") (pintype "passive"))
      (node (ref "DA6") (pin "2") (pinfunction "S1A_2") (pintype "passive"))
      (node (ref "DA6") (pin "6") (pinfunction "GND_6") (pintype "passive"))
      (node (ref "DA6") (pin "7") (pinfunction "S2B_7") (pintype "passive"))
      (node (ref "DA8") (pin "2") (pinfunction "GND_2") (pintype "passive"))
      (node (ref "DA8") (pin "3") (pinfunction "GND_3") (pintype "passive"))
      (node (ref "DA9") (pin "2") (pinfunction "S1A_2") (pintype "passive"))
      (node (ref "DA9") (pin "6") (pinfunction "GND_6") (pintype "passive"))
      (node (ref "DA9") (pin "7") (pinfunction "S2B_7") (pintype "passive"))
      (node (ref "R10") (pin "1") (pintype "passive"))
      (node (ref "R14") (pin "1") (pintype "passive"))
      (node (ref "R17") (pin "1") (pintype "passive"))
      (node (ref "R22") (pin "1") (pintype "passive"))
      (node (ref "TP10") (pin "1") (pinfunction "1_1") (pintype "passive"))
      (node (ref "TP7") (pin "1") (pinfunction "1_1") (pintype "passive"))
      (node (ref "TP8") (pin "1") (pinfunction "1_1") (pintype "passive"))
      (node (ref "TP9") (pin "1") (pinfunction "1_1") (pintype "passive"))
      (node (ref "VD1") (pin "2") (pinfunction "Cathode_2") (pintype "passive"))
      (node (ref "VD2") (pin "2") (pinfunction "Cathode_2") (pintype "passive"))
      (node (ref "VD3") (pin "2") (pinfunction "Cathode_2") (pintype "passive"))
      (node (ref "VD4") (pin "2") (pinfunction "Cathode_2") (pintype "passive"))
      (node (ref "VT1") (pin "2") (pinfunction "Suorce_2") (pintype "passive"))
      (node (ref "VT2") (pin "2") (pinfunction "Suorce_2") (pintype "passive"))
      (node (ref "VT3") (pin "2") (pinfunction "Suorce_2") (pintype "passive"))
      (node (ref "VT4") (pin "2") (pinfunction "Suorce_2") (pintype "passive"))
    )
    (net (code "26") (name "Net-(DA4-J-Pad1)") (class "Default")
      (node (ref "DA4") (pin "1") (pinfunction "J_1") (pintype "passive"))
      (node (ref "DA4") (pin "8") (pinfunction "J_8") (pintype "passive"))
    )
    (net (code "27") (name "Net-(DA4-OUT)") (class "Default")
      (node (ref "DA4") (pin "6") (pinfunction "OUT_6") (pintype "passive"))
      (node (ref "R8") (pin "1") (pintype "passive"))
    )
    (net (code "28") (name "Net-(DA4-REF)") (class "Default")
      (node (ref "C19") (pin "2") (pintype "passive"))
      (node (ref "DA4") (pin "5") (pinfunction "REF_5") (pintype "passive"))
      (node (ref "R10") (pin "2") (pintype "passive"))
      (node (ref "R9") (pin "1") (pintype "passive"))
    )
    (net (code "29") (name "Net-(DA5-Vin)") (class "Default")
      (node (ref "C16") (pin "2") (pintype "passive"))
      (node (ref "DA5") (pin "4") (pinfunction "Vin_4") (pintype "passive"))
      (node (ref "R8") (pin "2") (pintype "passive"))
    )
    (net (code "30") (name "Net-(DA6-D2)") (class "Default")
      (node (ref "C18") (pin "1") (pintype "passive"))
      (node (ref "DA6") (pin "9") (pinfunction "D2_9") (pintype "passive"))
    )
    (net (code "31") (name "Net-(DA7-J-Pad1)") (class "Default")
      (node (ref "DA7") (pin "1") (pinfunction "J_1") (pintype "passive"))
      (node (ref "DA7") (pin "8") (pinfunction "J_8") (pintype "passive"))
    )
    (net (code "32") (name "Net-(DA7-OUT)") (class "Default")
      (node (ref "DA7") (pin "6") (pinfunction "OUT_6") (pintype "passive"))
      (node (ref "R11") (pin "1") (pintype "passive"))
    )
    (net (code "33") (name "Net-(DA7-REF)") (class "Default")
      (node (ref "C27") (pin "2") (pintype "passive"))
      (node (ref "DA7") (pin "5") (pinfunction "REF_5") (pintype "passive"))
      (node (ref "R12") (pin "1") (pintype "passive"))
      (node (ref "R14") (pin "2") (pintype "passive"))
    )
    (net (code "34") (name "Net-(DA8-Vin)") (class "Default")
      (node (ref "C24") (pin "2") (pintype "passive"))
      (node (ref "DA8") (pin "4") (pinfunction "Vin_4") (pintype "passive"))
      (node (ref "R11") (pin "2") (pintype "passive"))
    )
    (net (code "35") (name "Net-(DA9-D2)") (class "Default")
      (node (ref "C30") (pin "1") (pintype "passive"))
      (node (ref "DA9") (pin "9") (pinfunction "D2_9") (pintype "passive"))
    )
    (net (code "36") (name "Net-(DA10-J-Pad1)") (class "Default")
      (node (ref "DA10") (pin "1") (pinfunction "J_1") (pintype "passive"))
      (node (ref "DA10") (pin "8") (pinfunction "J_8") (pintype "passive"))
    )
    (net (code "37") (name "Net-(DA10-OUT)") (class "Default")
      (node (ref "DA10") (pin "6") (pinfunction "OUT_6") (pintype "passive"))
      (node (ref "R15") (pin "1") (pintype "passive"))
    )
    (net (code "38") (name "Net-(DA10-REF)") (class "Default")
      (node (ref "C35") (pin "2") (pintype "passive"))
      (node (ref "DA10") (pin "5") (pinfunction "REF_5") (pintype "passive"))
      (node (ref "R16") (pin "1") (pintype "passive"))
      (node (ref "R17") (pin "2") (pintype "passive"))
    )
    (net (code "39") (name "Net-(DA11-Vin)") (class "Default")
      (node (ref "C31") (pin "2") (pintype "passive"))
      (node (ref "DA11") (pin "4") (pinfunction "Vin_4") (pintype "passive"))
      (node (ref "R15") (pin "2") (pintype "passive"))
    )
    (net (code "40") (name "Net-(DA12-D2)") (class "Default")
      (node (ref "C41") (pin "1") (pintype "passive"))
      (node (ref "DA12") (pin "9") (pinfunction "D2_9") (pintype "passive"))
    )
    (net (code "41") (name "Net-(DA13-D2)") (class "Default")
      (node (ref "C42") (pin "1") (pintype "passive"))
      (node (ref "DA13") (pin "9") (pinfunction "D2_9") (pintype "passive"))
    )
    (net (code "42") (name "Net-(DA14-J-Pad1)") (class "Default")
      (node (ref "DA14") (pin "1") (pinfunction "J_1") (pintype "passive"))
      (node (ref "DA14") (pin "8") (pinfunction "J_8") (pintype "passive"))
    )
    (net (code "43") (name "Net-(DA14-OUT)") (class "Default")
      (node (ref "DA14") (pin "6") (pinfunction "OUT_6") (pintype "passive"))
      (node (ref "R20") (pin "1") (pintype "passive"))
    )
    (net (code "44") (name "Net-(DA14-REF)") (class "Default")
      (node (ref "C44") (pin "2") (pintype "passive"))
      (node (ref "DA14") (pin "5") (pinfunction "REF_5") (pintype "passive"))
      (node (ref "R21") (pin "1") (pintype "passive"))
      (node (ref "R22") (pin "2") (pintype "passive"))
    )
    (net (code "45") (name "Net-(DA15-Vin)") (class "Default")
      (node (ref "C40") (pin "2") (pintype "passive"))
      (node (ref "DA15") (pin "4") (pinfunction "Vin_4") (pintype "passive"))
      (node (ref "R20") (pin "2") (pintype "passive"))
    )
    (net (code "46") (name "Net-(VD1-Anode)") (class "Default")
      (node (ref "C15") (pin "1") (pintype "passive"))
      (node (ref "R7") (pin "1") (pintype "passive"))
      (node (ref "VD1") (pin "1") (pinfunction "Anode_1") (pintype "passive"))
      (node (ref "VT1") (pin "1") (pinfunction "Suorce_1") (pintype "passive"))
    )
    (net (code "47") (name "Net-(VD2-Anode)") (class "Default")
      (node (ref "C26") (pin "1") (pintype "passive"))
      (node (ref "R13") (pin "1") (pintype "passive"))
      (node (ref "VD2") (pin "1") (pinfunction "Anode_1") (pintype "passive"))
      (node (ref "VT2") (pin "1") (pinfunction "Suorce_1") (pintype "passive"))
    )
    (net (code "48") (name "Net-(VD3-Anode)") (class "Default")
      (node (ref "C38") (pin "1") (pintype "passive"))
      (node (ref "R18") (pin "1") (pintype "passive"))
      (node (ref "VD3") (pin "1") (pinfunction "Anode_1") (pintype "passive"))
      (node (ref "VT3") (pin "1") (pinfunction "Suorce_1") (pintype "passive"))
    )
    (net (code "49") (name "Net-(VD4-Anode)") (class "Default")
      (node (ref "C39") (pin "1") (pintype "passive"))
      (node (ref "R19") (pin "1") (pintype "passive"))
      (node (ref "VD4") (pin "1") (pinfunction "Anode_1") (pintype "passive"))
      (node (ref "VT4") (pin "1") (pinfunction "Suorce_1") (pintype "passive"))
    )
  )
)
